# analog_tl494.net
KiCad netlist of a schematic drawn in Altium Designer
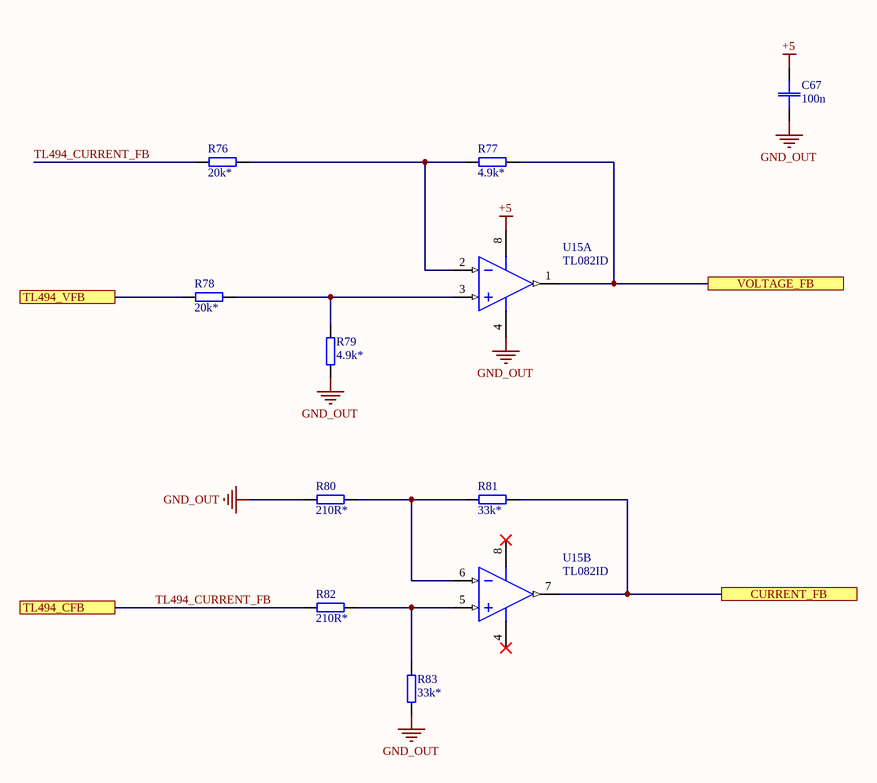
[diagram p0: analog_tl494.SchDoc]

(export (version "E")
  (design (tool "Eeschema 10.0.6"))
  (components
    (comp (ref "C67") (value "100n") (footprint "CAP: 0603") (libsource (lib "PASSIVE") (part "C_SMD")))
    (comp (ref "R76") (value "20k*") (footprint "RES: 0603") (libsource (lib "PASSIVE") (part "R_SMD")))
    (comp (ref "R77") (value "4.9k*") (footprint "RES: 0603") (libsource (lib "PASSIVE") (part "R_SMD")))
    (comp (ref "R78") (value "20k*") (footprint "RES: 0603") (libsource (lib "PASSIVE") (part "R_SMD")))
    (comp (ref "R79") (value "4.9k*") (footprint "RES: 0603") (libsource (lib "PASSIVE") (part "R_SMD")))
    (comp (ref "R80") (value "210R*") (footprint "RES: 0603") (libsource (lib "PASSIVE") (part "R_SMD")))
    (comp (ref "R81") (value "33k*") (footprint "RES: 0603") (libsource (lib "PASSIVE") (part "R_SMD")))
    (comp (ref "R82") (value "210R*") (footprint "RES: 0603") (libsource (lib "PASSIVE") (part "R_SMD")))
    (comp (ref "R83") (value "33k*") (footprint "RES: 0603") (libsource (lib "PASSIVE") (part "R_SMD")))
    (comp (ref "U15")
      (value "TL082ID")
      (footprint "TI-D8_N")
      (fields (field (name "MANUFACTURER") "Texas Instruments"))
      (libsource (lib "TI Amplifiers and Linear Operational Amplifier General Purpose") (part "TL082ID"))
    )
  )
  (nets
    (net (code "1") (name "+5") (class "Default")
      (node (ref "C67") (pin "2") (pinfunction "2_2") (pintype "passive"))
      (node (ref "U15") (pin "8") (pinfunction "VCC+_8") (pintype "power_in"))
    )
    (net (code "2") (name "/CURRENT_FB") (class "Default")
      (node (ref "R81") (pin "2") (pinfunction "2_2") (pintype "passive"))
      (node (ref "U15") (pin "7") (pinfunction "OUT2_7") (pintype "output"))
    )
    (net (code "3") (name "/TL494_CURRENT_FB") (class "Default")
      (node (ref "R76") (pin "1") (pinfunction "1_1") (pintype "passive"))
      (node (ref "R82") (pin "1") (pinfunction "1_1") (pintype "passive"))
    )
    (net (code "4") (name "/TL494_VFB") (class "Default")
      (node (ref "R78") (pin "1") (pinfunction "1_1") (pintype "passive"))
    )
    (net (code "5") (name "/VOLTAGE_FB") (class "Default")
      (node (ref "R77") (pin "2") (pinfunction "2_2") (pintype "passive"))
      (node (ref "U15") (pin "1") (pinfunction "OUT1_1") (pintype "output"))
    )
    (net (code "6") (name "GND_OUT") (class "Default")
      (node (ref "C67") (pin "1") (pinfunction "1_1") (pintype "passive"))
      (node (ref "R79") (pin "2") (pinfunction "2_2") (pintype "passive"))
      (node (ref "R80") (pin "1") (pinfunction "1_1") (pintype "passive"))
      (node (ref "R83") (pin "1") (pinfunction "1_1") (pintype "passive"))
      (node (ref "U15") (pin "4") (pinfunction "VCC-_4") (pintype "power_in"))
    )
    (net (code "7") (name "Net-(U15A-IN1+)") (class "Default")
      (node (ref "R78") (pin "2") (pinfunction "2_2") (pintype "passive"))
      (node (ref "R79") (pin "1") (pinfunction "1_1") (pintype "passive"))
      (node (ref "U15") (pin "3") (pinfunction "IN1+_3") (pintype "input"))
    )
    (net (code "8") (name "Net-(U15A-IN1-)") (class "Default")
      (node (ref "R76") (pin "2") (pinfunction "2_2") (pintype "passive"))
      (node (ref "R77") (pin "1") (pinfunction "1_1") (pintype "passive"))
      (node (ref "U15") (pin "2") (pinfunction "IN1-_2") (pintype "input"))
    )
    (net (code "9") (name "Net-(U15B-IN2+)") (class "Default")
      (node (ref "R82") (pin "2") (pinfunction "2_2") (pintype "passive"))
      (node (ref "R83") (pin "2") (pinfunction "2_2") (pintype "passive"))
      (node (ref "U15") (pin "5") (pinfunction "IN2+_5") (pintype "input"))
    )
    (net (code "10") (name "Net-(U15B-IN2-)") (class "Default")
      (node (ref "R80") (pin "2") (pinfunction "2_2") (pintype "passive"))
      (node (ref "R81") (pin "1") (pinfunction "1_1") (pintype "passive"))
      (node (ref "U15") (pin "6") (pinfunction "IN2-_6") (pintype "input"))
    )
    (net (code "11") (name "unconnected-(U15B-VCC+-Pad8)") (class "Default")
      (node (ref "U15") (pin "8") (pinfunction "VCC+_8") (pintype "power_in+no_connect"))
    )
    (net (code "12") (name "unconnected-(U15B-VCC--Pad4)") (class "Default")
      (node (ref "U15") (pin "4") (pinfunction "VCC-_4") (pintype "power_in+no_connect"))
    )
  )
)
